# circut-v2.net
KiCad netlist of a schematic drawn in EAGLE
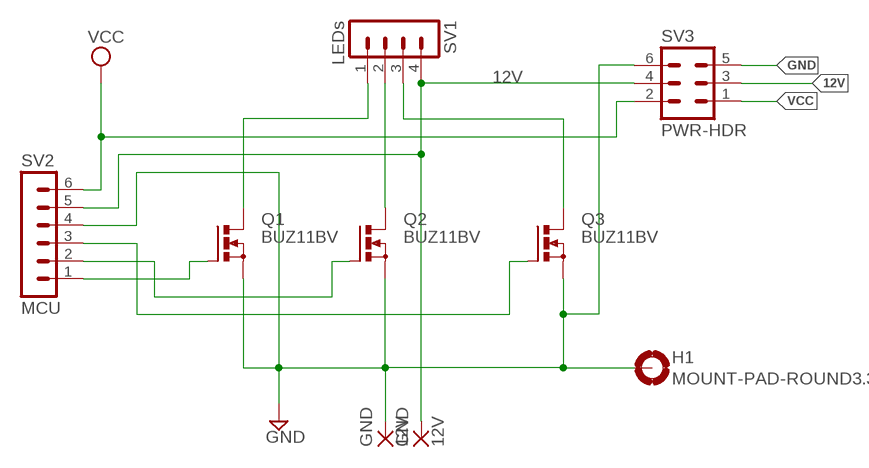
[diagram p0: schematic, sheet 1]

(export (version "E")
  (design (tool "Eeschema 10.0.6"))
  (components
    (comp (ref "12V")
      (value "12V")
      (footprint "eagle-import:3,17_1,3")
      (libsource (lib "eagle-import") (part "3,17/1,3"))
    )
    (comp (ref "GND")
      (value "GND")
      (footprint "eagle-import:3,17_1,3")
      (libsource (lib "eagle-import") (part "3,17/1,3"))
    )
    (comp (ref "H1")
      (value "MOUNT-PAD-ROUND3.3")
      (footprint "eagle-import:3,3-PAD")
      (libsource (lib "eagle-import") (part "MOUNT-PAD-ROUND3.3"))
    )
    (comp (ref "Q1")
      (value "BUZ11BV")
      (footprint "eagle-import:TO220BV")
      (libsource (lib "eagle-import") (part "BUZ11BV"))
    )
    (comp (ref "Q2")
      (value "BUZ11BV")
      (footprint "eagle-import:TO220BV")
      (libsource (lib "eagle-import") (part "BUZ11BV"))
    )
    (comp (ref "Q3")
      (value "BUZ11BV")
      (footprint "eagle-import:TO220BV")
      (libsource (lib "eagle-import") (part "BUZ11BV"))
    )
    (comp (ref "SV1")
      (value "LEDs")
      (footprint "eagle-import:MA04-1")
      (libsource (lib "eagle-import") (part "MA04-1"))
    )
    (comp (ref "SV2")
      (value "MCU")
      (footprint "eagle-import:MA06-1")
      (libsource (lib "eagle-import") (part "MA06-1"))
    )
    (comp (ref "SV3")
      (value "PWR-HDR")
      (footprint "eagle-import:MA03-2")
      (libsource (lib "eagle-import") (part "MA03-2"))
    )
  )
  (nets
    (net (code "1") (name "12V") (class "Default")
      (node (ref "12V") (pin "1") (pinfunction "P_1") (pintype "passive"))
      (node (ref "SV1") (pin "4") (pinfunction "4_4") (pintype "passive"))
      (node (ref "SV2") (pin "5") (pinfunction "5_5") (pintype "passive"))
      (node (ref "SV3") (pin "3") (pinfunction "3_3") (pintype "passive"))
      (node (ref "SV3") (pin "4") (pinfunction "4_4") (pintype "passive"))
    )
    (net (code "2") (name "GND") (class "Default")
      (node (ref "GND") (pin "1") (pinfunction "P_1") (pintype "passive"))
      (node (ref "H1") (pin "B3,3") (pinfunction "MOUNT_B3,3") (pintype "passive"))
      (node (ref "Q1") (pin "S") (pinfunction "S_S") (pintype "passive"))
      (node (ref "Q2") (pin "S") (pinfunction "S_S") (pintype "passive"))
      (node (ref "Q3") (pin "S") (pinfunction "S_S") (pintype "passive"))
      (node (ref "SV2") (pin "4") (pinfunction "4_4") (pintype "passive"))
      (node (ref "SV3") (pin "5") (pinfunction "5_5") (pintype "passive"))
      (node (ref "SV3") (pin "6") (pinfunction "6_6") (pintype "passive"))
    )
    (net (code "3") (name "Net-(Q1-PadD)") (class "Default")
      (node (ref "Q1") (pin "D") (pinfunction "D_D") (pintype "passive"))
      (node (ref "SV1") (pin "1") (pinfunction "1_1") (pintype "passive"))
    )
    (net (code "4") (name "Net-(Q1-PadG)") (class "Default")
      (node (ref "Q1") (pin "G") (pinfunction "G_G") (pintype "passive"))
      (node (ref "SV2") (pin "1") (pinfunction "1_1") (pintype "passive"))
    )
    (net (code "5") (name "Net-(Q2-PadD)") (class "Default")
      (node (ref "Q2") (pin "D") (pinfunction "D_D") (pintype "passive"))
      (node (ref "SV1") (pin "2") (pinfunction "2_2") (pintype "passive"))
    )
    (net (code "6") (name "Net-(Q2-PadG)") (class "Default")
      (node (ref "Q2") (pin "G") (pinfunction "G_G") (pintype "passive"))
      (node (ref "SV2") (pin "2") (pinfunction "2_2") (pintype "passive"))
    )
    (net (code "7") (name "Net-(Q3-PadD)") (class "Default")
      (node (ref "Q3") (pin "D") (pinfunction "D_D") (pintype "passive"))
      (node (ref "SV1") (pin "3") (pinfunction "3_3") (pintype "passive"))
    )
    (net (code "8") (name "Net-(Q3-PadG)") (class "Default")
      (node (ref "Q3") (pin "G") (pinfunction "G_G") (pintype "passive"))
      (node (ref "SV2") (pin "3") (pinfunction "3_3") (pintype "passive"))
    )
    (net (code "9") (name "VCC") (class "Default")
      (node (ref "SV2") (pin "6") (pinfunction "6_6") (pintype "passive"))
      (node (ref "SV3") (pin "1") (pinfunction "1_1") (pintype "passive"))
      (node (ref "SV3") (pin "2") (pinfunction "2_2") (pintype "passive"))
    )
  )
)
